# TRANSFORMER_RJ45.net
KiCad netlist of a schematic drawn in Altium Designer
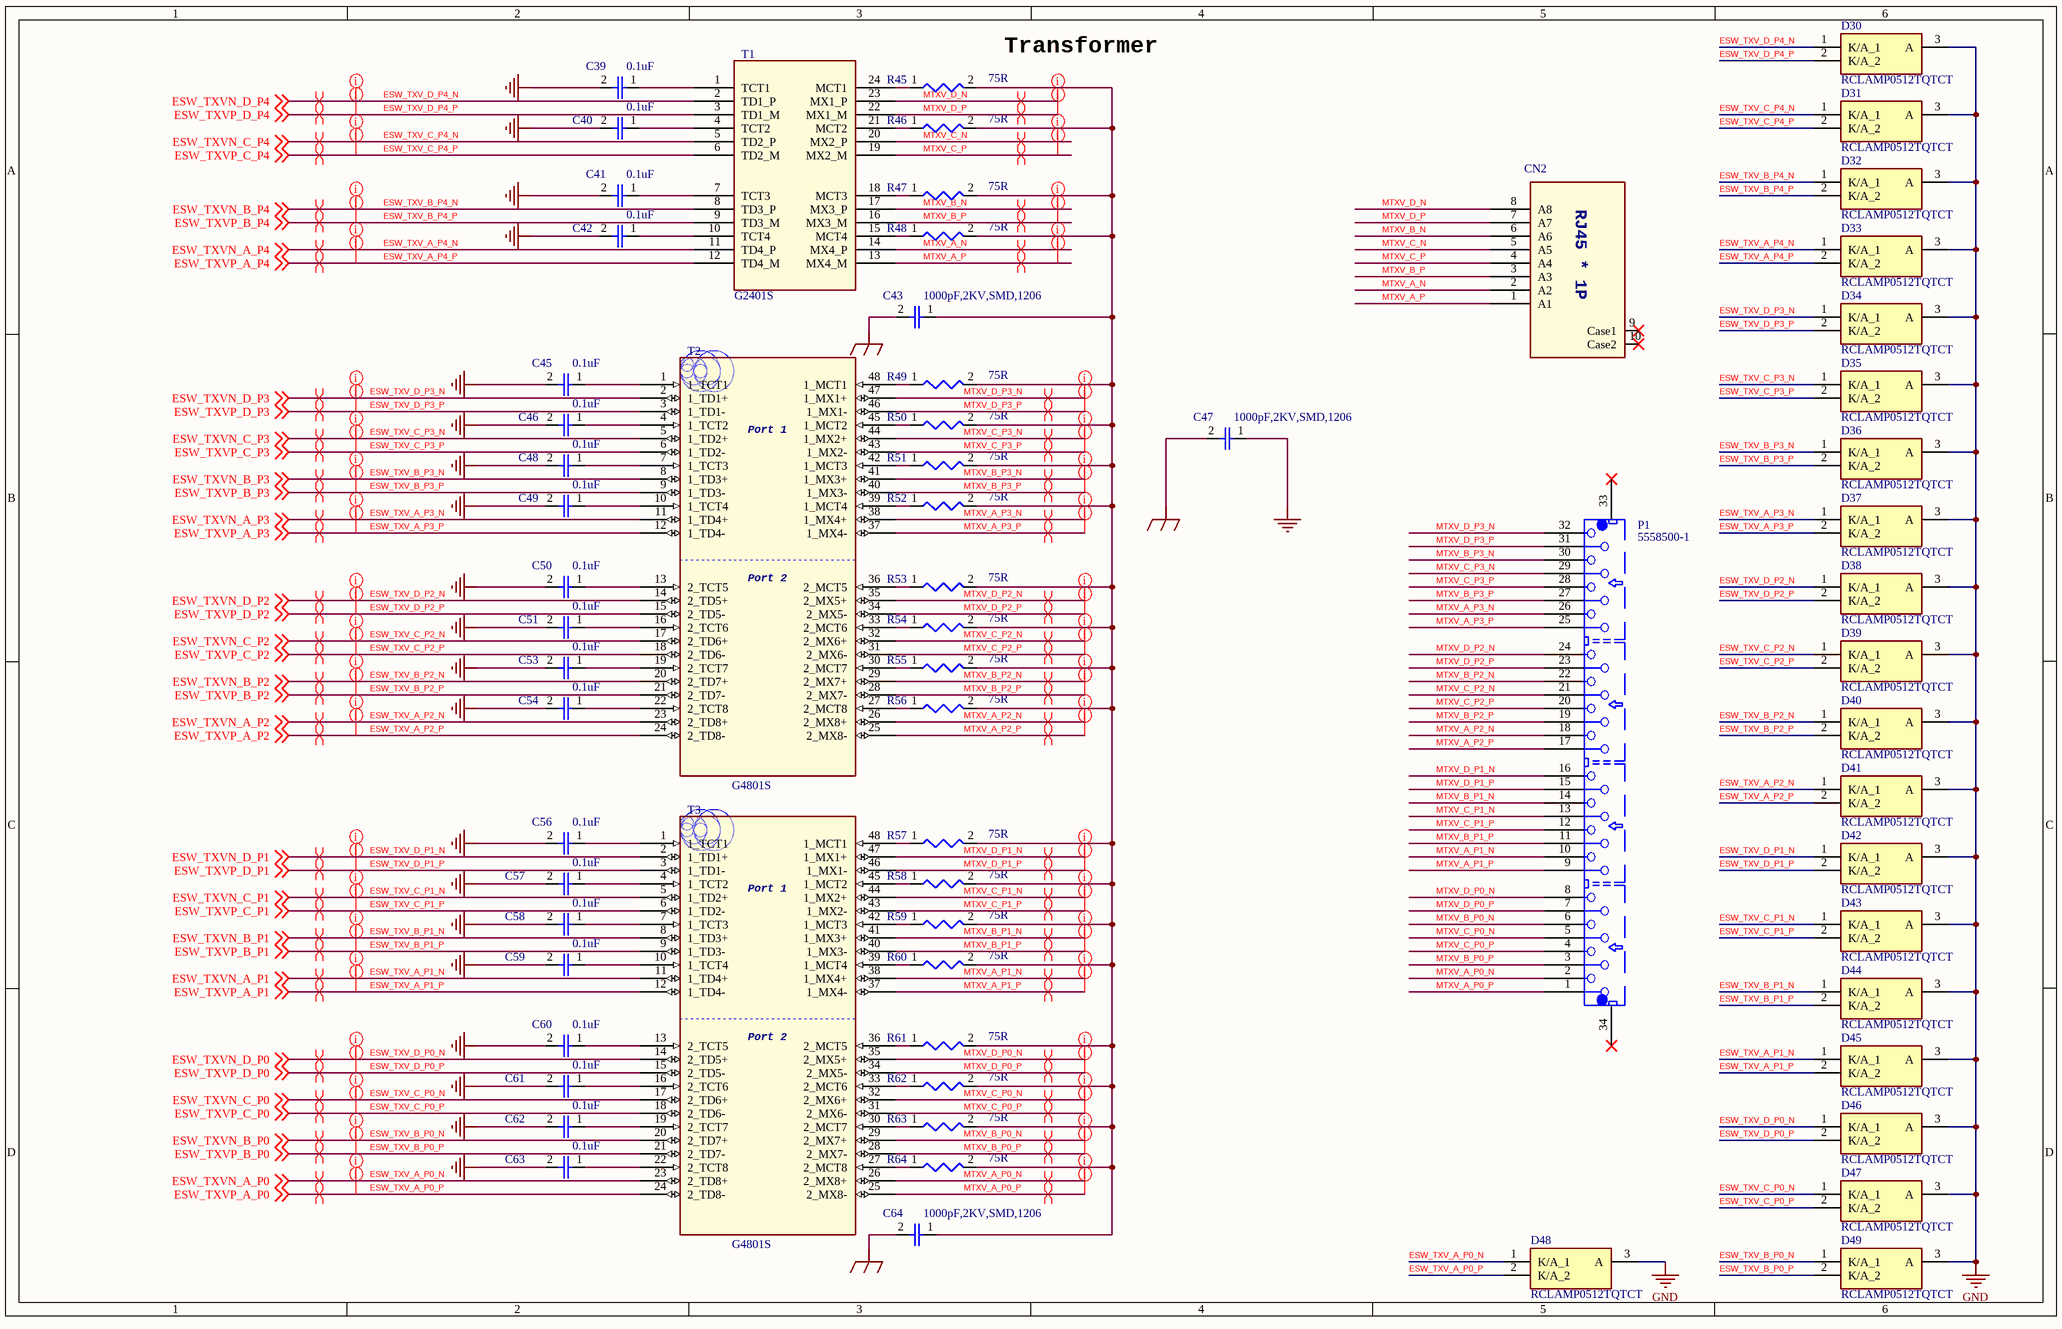
[diagram p0: TRANSFORMER_RJ45.SchDoc]

(export (version "E")
  (design (tool "Eeschema 10.0.6"))
  (components
    (comp (ref "C39") (value "0.1uF") (footprint "0402-C") (libsource (lib "OOLITEV8") (part "CAP")))
    (comp (ref "C40") (value "0.1uF") (footprint "0402-C") (libsource (lib "OOLITEV8") (part "CAP")))
    (comp (ref "C41") (value "0.1uF") (footprint "0402-C") (libsource (lib "OOLITEV8") (part "CAP")))
    (comp (ref "C42") (value "0.1uF") (footprint "0402-C") (libsource (lib "OOLITEV8") (part "CAP")))
    (comp (ref "C43")
      (value "1000pF,2KV,SMD,1206")
      (footprint "1206-C")
      (libsource (lib "OOLITEV8") (part "CAP"))
    )
    (comp (ref "C45") (value "0.1uF") (footprint "0402-C") (libsource (lib "OOLITEV8") (part "CAP")))
    (comp (ref "C46") (value "0.1uF") (footprint "0402-C") (libsource (lib "OOLITEV8") (part "CAP")))
    (comp (ref "C47")
      (value "1000pF,2KV,SMD,1206")
      (footprint "1206-C")
      (libsource (lib "OOLITEV8") (part "CAP"))
    )
    (comp (ref "C48") (value "0.1uF") (footprint "0402-C") (libsource (lib "OOLITEV8") (part "CAP")))
    (comp (ref "C49") (value "0.1uF") (footprint "0402-C") (libsource (lib "OOLITEV8") (part "CAP")))
    (comp (ref "C50") (value "0.1uF") (footprint "0402-C") (libsource (lib "OOLITEV8") (part "CAP")))
    (comp (ref "C51") (value "0.1uF") (footprint "0402-C") (libsource (lib "OOLITEV8") (part "CAP")))
    (comp (ref "C53") (value "0.1uF") (footprint "0402-C") (libsource (lib "OOLITEV8") (part "CAP")))
    (comp (ref "C54") (value "0.1uF") (footprint "0402-C") (libsource (lib "OOLITEV8") (part "CAP")))
    (comp (ref "C56") (value "0.1uF") (footprint "0402-C") (libsource (lib "OOLITEV8") (part "CAP")))
    (comp (ref "C57") (value "0.1uF") (footprint "0402-C") (libsource (lib "OOLITEV8") (part "CAP")))
    (comp (ref "C58") (value "0.1uF") (footprint "0402-C") (libsource (lib "OOLITEV8") (part "CAP")))
    (comp (ref "C59") (value "0.1uF") (footprint "0402-C") (libsource (lib "OOLITEV8") (part "CAP")))
    (comp (ref "C60") (value "0.1uF") (footprint "0402-C") (libsource (lib "OOLITEV8") (part "CAP")))
    (comp (ref "C61") (value "0.1uF") (footprint "0402-C") (libsource (lib "OOLITEV8") (part "CAP")))
    (comp (ref "C62") (value "0.1uF") (footprint "0402-C") (libsource (lib "OOLITEV8") (part "CAP")))
    (comp (ref "C63") (value "0.1uF") (footprint "0402-C") (libsource (lib "OOLITEV8") (part "CAP")))
    (comp (ref "C64")
      (value "1000pF,2KV,SMD,1206")
      (footprint "1206-C")
      (libsource (lib "OOLITEV8") (part "CAP"))
    )
    (comp (ref "CN2")
      (value "6116518-1")
      (footprint "BEL_SS-6488-NF")
      (libsource (lib "OOLITEV8") (part "6116518-1"))
    )
    (comp (ref "D30")
      (value "RCLAMP0512TQTCT")
      (footprint "RCLAMP0512TQTCT")
      (description "Diode")
      (fields (field (name "MOUSER PART NUMBER") "947-RCLAMP0512TQTCT"))
      (libsource (lib "SamacSys") (part "RCLAMP0512TQTCT"))
    )
    (comp (ref "D31")
      (value "RCLAMP0512TQTCT")
      (footprint "RCLAMP0512TQTCT")
      (description "Diode")
      (fields (field (name "MOUSER PART NUMBER") "947-RCLAMP0512TQTCT"))
      (libsource (lib "SamacSys") (part "RCLAMP0512TQTCT"))
    )
    (comp (ref "D32")
      (value "RCLAMP0512TQTCT")
      (footprint "RCLAMP0512TQTCT")
      (description "Diode")
      (fields (field (name "MOUSER PART NUMBER") "947-RCLAMP0512TQTCT"))
      (libsource (lib "SamacSys") (part "RCLAMP0512TQTCT"))
    )
    (comp (ref "D33")
      (value "RCLAMP0512TQTCT")
      (footprint "RCLAMP0512TQTCT")
      (description "Diode")
      (fields (field (name "MOUSER PART NUMBER") "947-RCLAMP0512TQTCT"))
      (libsource (lib "SamacSys") (part "RCLAMP0512TQTCT"))
    )
    (comp (ref "D34")
      (value "RCLAMP0512TQTCT")
      (footprint "RCLAMP0512TQTCT")
      (description "Diode")
      (fields (field (name "MOUSER PART NUMBER") "947-RCLAMP0512TQTCT"))
      (libsource (lib "SamacSys") (part "RCLAMP0512TQTCT"))
    )
    (comp (ref "D35")
      (value "RCLAMP0512TQTCT")
      (footprint "RCLAMP0512TQTCT")
      (description "Diode")
      (fields (field (name "MOUSER PART NUMBER") "947-RCLAMP0512TQTCT"))
      (libsource (lib "SamacSys") (part "RCLAMP0512TQTCT"))
    )
    (comp (ref "D36")
      (value "RCLAMP0512TQTCT")
      (footprint "RCLAMP0512TQTCT")
      (description "Diode")
      (fields (field (name "MOUSER PART NUMBER") "947-RCLAMP0512TQTCT"))
      (libsource (lib "SamacSys") (part "RCLAMP0512TQTCT"))
    )
    (comp (ref "D37")
      (value "RCLAMP0512TQTCT")
      (footprint "RCLAMP0512TQTCT")
      (description "Diode")
      (fields (field (name "MOUSER PART NUMBER") "947-RCLAMP0512TQTCT"))
      (libsource (lib "SamacSys") (part "RCLAMP0512TQTCT"))
    )
    (comp (ref "D38")
      (value "RCLAMP0512TQTCT")
      (footprint "RCLAMP0512TQTCT")
      (description "Diode")
      (fields (field (name "MOUSER PART NUMBER") "947-RCLAMP0512TQTCT"))
      (libsource (lib "SamacSys") (part "RCLAMP0512TQTCT"))
    )
    (comp (ref "D39")
      (value "RCLAMP0512TQTCT")
      (footprint "RCLAMP0512TQTCT")
      (description "Diode")
      (fields (field (name "MOUSER PART NUMBER") "947-RCLAMP0512TQTCT"))
      (libsource (lib "SamacSys") (part "RCLAMP0512TQTCT"))
    )
    (comp (ref "D40")
      (value "RCLAMP0512TQTCT")
      (footprint "RCLAMP0512TQTCT")
      (description "Diode")
      (fields (field (name "MOUSER PART NUMBER") "947-RCLAMP0512TQTCT"))
      (libsource (lib "SamacSys") (part "RCLAMP0512TQTCT"))
    )
    (comp (ref "D41")
      (value "RCLAMP0512TQTCT")
      (footprint "RCLAMP0512TQTCT")
      (description "Diode")
      (fields (field (name "MOUSER PART NUMBER") "947-RCLAMP0512TQTCT"))
      (libsource (lib "SamacSys") (part "RCLAMP0512TQTCT"))
    )
    (comp (ref "D42")
      (value "RCLAMP0512TQTCT")
      (footprint "RCLAMP0512TQTCT")
      (description "Diode")
      (fields (field (name "MOUSER PART NUMBER") "947-RCLAMP0512TQTCT"))
      (libsource (lib "SamacSys") (part "RCLAMP0512TQTCT"))
    )
    (comp (ref "D43")
      (value "RCLAMP0512TQTCT")
      (footprint "RCLAMP0512TQTCT")
      (description "Diode")
      (fields (field (name "MOUSER PART NUMBER") "947-RCLAMP0512TQTCT"))
      (libsource (lib "SamacSys") (part "RCLAMP0512TQTCT"))
    )
    (comp (ref "D44")
      (value "RCLAMP0512TQTCT")
      (footprint "RCLAMP0512TQTCT")
      (description "Diode")
      (fields (field (name "MOUSER PART NUMBER") "947-RCLAMP0512TQTCT"))
      (libsource (lib "SamacSys") (part "RCLAMP0512TQTCT"))
    )
    (comp (ref "D45")
      (value "RCLAMP0512TQTCT")
      (footprint "RCLAMP0512TQTCT")
      (description "Diode")
      (fields (field (name "MOUSER PART NUMBER") "947-RCLAMP0512TQTCT"))
      (libsource (lib "SamacSys") (part "RCLAMP0512TQTCT"))
    )
    (comp (ref "D46")
      (value "RCLAMP0512TQTCT")
      (footprint "RCLAMP0512TQTCT")
      (description "Diode")
      (fields (field (name "MOUSER PART NUMBER") "947-RCLAMP0512TQTCT"))
      (libsource (lib "SamacSys") (part "RCLAMP0512TQTCT"))
    )
    (comp (ref "D47")
      (value "RCLAMP0512TQTCT")
      (footprint "RCLAMP0512TQTCT")
      (description "Diode")
      (fields (field (name "MOUSER PART NUMBER") "947-RCLAMP0512TQTCT"))
      (libsource (lib "SamacSys") (part "RCLAMP0512TQTCT"))
    )
    (comp (ref "D48")
      (value "RCLAMP0512TQTCT")
      (footprint "RCLAMP0512TQTCT")
      (description "Diode")
      (fields (field (name "MOUSER PART NUMBER") "947-RCLAMP0512TQTCT"))
      (libsource (lib "SamacSys") (part "RCLAMP0512TQTCT"))
    )
    (comp (ref "D49")
      (value "RCLAMP0512TQTCT")
      (footprint "RCLAMP0512TQTCT")
      (description "Diode")
      (fields (field (name "MOUSER PART NUMBER") "947-RCLAMP0512TQTCT"))
      (libsource (lib "SamacSys") (part "RCLAMP0512TQTCT"))
    )
    (comp (ref "P1")
      (value "5558500-1")
      (footprint "CONN_ARJ14A-MESA-MU2")
      (libsource (lib "OOLITEV8") (part "5558500-1"))
    )
    (comp (ref "R45") (value "75R") (footprint "0402-R") (libsource (lib "OOLITEV8") (part "Res")))
    (comp (ref "R46") (value "75R") (footprint "0402-R") (libsource (lib "OOLITEV8") (part "Res")))
    (comp (ref "R47") (value "75R") (footprint "0402-R") (libsource (lib "OOLITEV8") (part "Res")))
    (comp (ref "R48") (value "75R") (footprint "0402-R") (libsource (lib "OOLITEV8") (part "Res")))
    (comp (ref "R49") (value "75R") (footprint "0402-R") (libsource (lib "OOLITEV8") (part "Res")))
    (comp (ref "R50") (value "75R") (footprint "0402-R") (libsource (lib "OOLITEV8") (part "Res")))
    (comp (ref "R51") (value "75R") (footprint "0402-R") (libsource (lib "OOLITEV8") (part "Res")))
    (comp (ref "R52") (value "75R") (footprint "0402-R") (libsource (lib "OOLITEV8") (part "Res")))
    (comp (ref "R53") (value "75R") (footprint "0402-R") (libsource (lib "OOLITEV8") (part "Res")))
    (comp (ref "R54") (value "75R") (footprint "0402-R") (libsource (lib "OOLITEV8") (part "Res")))
    (comp (ref "R55") (value "75R") (footprint "0402-R") (libsource (lib "OOLITEV8") (part "Res")))
    (comp (ref "R56") (value "75R") (footprint "0402-R") (libsource (lib "OOLITEV8") (part "Res")))
    (comp (ref "R57") (value "75R") (footprint "0402-R") (libsource (lib "OOLITEV8") (part "Res")))
    (comp (ref "R58") (value "75R") (footprint "0402-R") (libsource (lib "OOLITEV8") (part "Res")))
    (comp (ref "R59") (value "75R") (footprint "0402-R") (libsource (lib "OOLITEV8") (part "Res")))
    (comp (ref "R60") (value "75R") (footprint "0402-R") (libsource (lib "OOLITEV8") (part "Res")))
    (comp (ref "R61") (value "75R") (footprint "0402-R") (libsource (lib "OOLITEV8") (part "Res")))
    (comp (ref "R62") (value "75R") (footprint "0402-R") (libsource (lib "OOLITEV8") (part "Res")))
    (comp (ref "R63") (value "75R") (footprint "0402-R") (libsource (lib "OOLITEV8") (part "Res")))
    (comp (ref "R64") (value "75R") (footprint "0402-R") (libsource (lib "OOLITEV8") (part "Res")))
    (comp (ref "T1")
      (value "G2401S")
      (footprint "SOP127P1600X572-24N")
      (description "Audio Transformers / Signal Transformers 1000BaseT SMD NonPoE 350uH .65Ohms 1-Por")
      (libsource (lib "OOLITEV8") (part "G2401S"))
    )
    (comp (ref "T2")
      (value "G4801S")
      (footprint "NV6")
      (description "Audio Transformers / Signal Transformers GIGABIT ISO MOD SMD 48P 2-Port w/Choke")
      (libsource (lib "OOLITEV8") (part "G4801S"))
    )
    (comp (ref "T3")
      (value "G4801S")
      (footprint "NV6")
      (description "Audio Transformers / Signal Transformers GIGABIT ISO MOD SMD 48P 2-Port w/Choke")
      (libsource (lib "OOLITEV8") (part "G4801S"))
    )
  )
  (nets
    (net (code "1") (name "/MTXV_A_N") (class "Default")
      (node (ref "CN2") (pin "2") (pinfunction "A2_2") (pintype "passive"))
      (node (ref "T1") (pin "14") (pinfunction "MX4_P_14") (pintype "passive"))
    )
    (net (code "2") (name "/MTXV_A_P") (class "Default")
      (node (ref "CN2") (pin "1") (pinfunction "A1_1") (pintype "passive"))
      (node (ref "T1") (pin "13") (pinfunction "MX4_M_13") (pintype "passive"))
    )
    (net (code "3") (name "/MTXV_A_P0_N") (class "Default")
      (node (ref "P1") (pin "2") (pinfunction "2_2") (pintype "passive"))
      (node (ref "T3") (pin "26") (pinfunction "2_MX8+_26") (pintype "bidirectional"))
    )
    (net (code "4") (name "/MTXV_A_P0_P") (class "Default")
      (node (ref "P1") (pin "1") (pinfunction "1_1") (pintype "passive"))
      (node (ref "T3") (pin "25") (pinfunction "2_MX8-_25") (pintype "bidirectional"))
    )
    (net (code "5") (name "/MTXV_A_P1_N") (class "Default")
      (node (ref "P1") (pin "10") (pinfunction "10_10") (pintype "passive"))
      (node (ref "T3") (pin "38") (pinfunction "1_MX4+_38") (pintype "bidirectional"))
    )
    (net (code "6") (name "/MTXV_A_P1_P") (class "Default")
      (node (ref "P1") (pin "9") (pinfunction "9_9") (pintype "passive"))
      (node (ref "T3") (pin "37") (pinfunction "1_MX4-_37") (pintype "bidirectional"))
    )
    (net (code "7") (name "/MTXV_A_P2_N") (class "Default")
      (node (ref "P1") (pin "18") (pinfunction "18_18") (pintype "passive"))
      (node (ref "T2") (pin "26") (pinfunction "2_MX8+_26") (pintype "bidirectional"))
    )
    (net (code "8") (name "/MTXV_A_P2_P") (class "Default")
      (node (ref "P1") (pin "17") (pinfunction "17_17") (pintype "passive"))
      (node (ref "T2") (pin "25") (pinfunction "2_MX8-_25") (pintype "bidirectional"))
    )
    (net (code "9") (name "/MTXV_A_P3_N") (class "Default")
      (node (ref "P1") (pin "26") (pinfunction "26_26") (pintype "passive"))
      (node (ref "T2") (pin "38") (pinfunction "1_MX4+_38") (pintype "bidirectional"))
    )
    (net (code "10") (name "/MTXV_A_P3_P") (class "Default")
      (node (ref "P1") (pin "25") (pinfunction "25_25") (pintype "passive"))
      (node (ref "T2") (pin "37") (pinfunction "1_MX4-_37") (pintype "bidirectional"))
    )
    (net (code "11") (name "/MTXV_B_N") (class "Default")
      (node (ref "CN2") (pin "6") (pinfunction "A6_6") (pintype "passive"))
      (node (ref "T1") (pin "17") (pinfunction "MX3_P_17") (pintype "passive"))
    )
    (net (code "12") (name "/MTXV_B_P") (class "Default")
      (node (ref "CN2") (pin "3") (pinfunction "A3_3") (pintype "passive"))
      (node (ref "T1") (pin "16") (pinfunction "MX3_M_16") (pintype "passive"))
    )
    (net (code "13") (name "/MTXV_B_P0_N") (class "Default")
      (node (ref "P1") (pin "6") (pinfunction "6_6") (pintype "passive"))
      (node (ref "T3") (pin "29") (pinfunction "2_MX7+_29") (pintype "bidirectional"))
    )
    (net (code "14") (name "/MTXV_B_P0_P") (class "Default")
      (node (ref "P1") (pin "3") (pinfunction "3_3") (pintype "passive"))
      (node (ref "T3") (pin "28") (pinfunction "2_MX7-_28") (pintype "bidirectional"))
    )
    (net (code "15") (name "/MTXV_B_P1_N") (class "Default")
      (node (ref "P1") (pin "14") (pinfunction "14_14") (pintype "passive"))
      (node (ref "T3") (pin "41") (pinfunction "1_MX3+_41") (pintype "bidirectional"))
    )
    (net (code "16") (name "/MTXV_B_P1_P") (class "Default")
      (node (ref "P1") (pin "11") (pinfunction "11_11") (pintype "passive"))
      (node (ref "T3") (pin "40") (pinfunction "1_MX3-_40") (pintype "bidirectional"))
    )
    (net (code "17") (name "/MTXV_B_P2_N") (class "Default")
      (node (ref "P1") (pin "22") (pinfunction "22_22") (pintype "passive"))
      (node (ref "T2") (pin "29") (pinfunction "2_MX7+_29") (pintype "bidirectional"))
    )
    (net (code "18") (name "/MTXV_B_P2_P") (class "Default")
      (node (ref "P1") (pin "19") (pinfunction "19_19") (pintype "passive"))
      (node (ref "T2") (pin "28") (pinfunction "2_MX7-_28") (pintype "bidirectional"))
    )
    (net (code "19") (name "/MTXV_B_P3_N") (class "Default")
      (node (ref "P1") (pin "30") (pinfunction "30_30") (pintype "passive"))
      (node (ref "T2") (pin "41") (pinfunction "1_MX3+_41") (pintype "bidirectional"))
    )
    (net (code "20") (name "/MTXV_B_P3_P") (class "Default")
      (node (ref "P1") (pin "27") (pinfunction "27_27") (pintype "passive"))
      (node (ref "T2") (pin "40") (pinfunction "1_MX3-_40") (pintype "bidirectional"))
    )
    (net (code "21") (name "/MTXV_C_N") (class "Default")
      (node (ref "CN2") (pin "5") (pinfunction "A5_5") (pintype "passive"))
      (node (ref "T1") (pin "20") (pinfunction "MX2_P_20") (pintype "passive"))
    )
    (net (code "22") (name "/MTXV_C_P") (class "Default")
      (node (ref "CN2") (pin "4") (pinfunction "A4_4") (pintype "passive"))
      (node (ref "T1") (pin "19") (pinfunction "MX2_M_19") (pintype "passive"))
    )
    (net (code "23") (name "/MTXV_C_P0_N") (class "Default")
      (node (ref "P1") (pin "5") (pinfunction "5_5") (pintype "passive"))
      (node (ref "T3") (pin "32") (pinfunction "2_MX6+_32") (pintype "bidirectional"))
    )
    (net (code "24") (name "/MTXV_C_P0_P") (class "Default")
      (node (ref "P1") (pin "4") (pinfunction "4_4") (pintype "passive"))
      (node (ref "T3") (pin "31") (pinfunction "2_MX6-_31") (pintype "bidirectional"))
    )
    (net (code "25") (name "/MTXV_C_P1_N") (class "Default")
      (node (ref "P1") (pin "13") (pinfunction "13_13") (pintype "passive"))
      (node (ref "T3") (pin "44") (pinfunction "1_MX2+_44") (pintype "bidirectional"))
    )
    (net (code "26") (name "/MTXV_C_P1_P") (class "Default")
      (node (ref "P1") (pin "12") (pinfunction "12_12") (pintype "passive"))
      (node (ref "T3") (pin "43") (pinfunction "1_MX2-_43") (pintype "bidirectional"))
    )
    (net (code "27") (name "/MTXV_C_P2_N") (class "Default")
      (node (ref "P1") (pin "21") (pinfunction "21_21") (pintype "passive"))
      (node (ref "T2") (pin "32") (pinfunction "2_MX6+_32") (pintype "bidirectional"))
    )
    (net (code "28") (name "/MTXV_C_P2_P") (class "Default")
      (node (ref "P1") (pin "20") (pinfunction "20_20") (pintype "passive"))
      (node (ref "T2") (pin "31") (pinfunction "2_MX6-_31") (pintype "bidirectional"))
    )
    (net (code "29") (name "/MTXV_C_P3_N") (class "Default")
      (node (ref "P1") (pin "29") (pinfunction "29_29") (pintype "passive"))
      (node (ref "T2") (pin "44") (pinfunction "1_MX2+_44") (pintype "bidirectional"))
    )
    (net (code "30") (name "/MTXV_C_P3_P") (class "Default")
      (node (ref "P1") (pin "28") (pinfunction "28_28") (pintype "passive"))
      (node (ref "T2") (pin "43") (pinfunction "1_MX2-_43") (pintype "bidirectional"))
    )
    (net (code "31") (name "/MTXV_D_N") (class "Default")
      (node (ref "CN2") (pin "8") (pinfunction "A8_8") (pintype "passive"))
      (node (ref "T1") (pin "23") (pinfunction "MX1_P_23") (pintype "passive"))
    )
    (net (code "32") (name "/MTXV_D_P") (class "Default")
      (node (ref "CN2") (pin "7") (pinfunction "A7_7") (pintype "passive"))
      (node (ref "T1") (pin "22") (pinfunction "MX1_M_22") (pintype "passive"))
    )
    (net (code "33") (name "/MTXV_D_P0_N") (class "Default")
      (node (ref "P1") (pin "8") (pinfunction "8_8") (pintype "passive"))
      (node (ref "T3") (pin "35") (pinfunction "2_MX5+_35") (pintype "bidirectional"))
    )
    (net (code "34") (name "/MTXV_D_P0_P") (class "Default")
      (node (ref "P1") (pin "7") (pinfunction "7_7") (pintype "passive"))
      (node (ref "T3") (pin "34") (pinfunction "2_MX5-_34") (pintype "bidirectional"))
    )
    (net (code "35") (name "/MTXV_D_P1_N") (class "Default")
      (node (ref "P1") (pin "16") (pinfunction "16_16") (pintype "passive"))
      (node (ref "T3") (pin "47") (pinfunction "1_MX1+_47") (pintype "bidirectional"))
    )
    (net (code "36") (name "/MTXV_D_P1_P") (class "Default")
      (node (ref "P1") (pin "15") (pinfunction "15_15") (pintype "passive"))
      (node (ref "T3") (pin "46") (pinfunction "1_MX1-_46") (pintype "bidirectional"))
    )
    (net (code "37") (name "/MTXV_D_P2_N") (class "Default")
      (node (ref "P1") (pin "24") (pinfunction "24_24") (pintype "passive"))
      (node (ref "T2") (pin "35") (pinfunction "2_MX5+_35") (pintype "bidirectional"))
    )
    (net (code "38") (name "/MTXV_D_P2_P") (class "Default")
      (node (ref "P1") (pin "23") (pinfunction "23_23") (pintype "passive"))
      (node (ref "T2") (pin "34") (pinfunction "2_MX5-_34") (pintype "bidirectional"))
    )
    (net (code "39") (name "/MTXV_D_P3_N") (class "Default")
      (node (ref "P1") (pin "32") (pinfunction "32_32") (pintype "passive"))
      (node (ref "T2") (pin "47") (pinfunction "1_MX1+_47") (pintype "bidirectional"))
    )
    (net (code "40") (name "/MTXV_D_P3_P") (class "Default")
      (node (ref "P1") (pin "31") (pinfunction "31_31") (pintype "passive"))
      (node (ref "T2") (pin "46") (pinfunction "1_MX1-_46") (pintype "bidirectional"))
    )
    (net (code "41") (name "CHGND_GE_A") (class "Default")
      (node (ref "C43") (pin "2") (pinfunction "2_2") (pintype "passive"))
      (node (ref "C47") (pin "2") (pinfunction "2_2") (pintype "passive"))
      (node (ref "C64") (pin "2") (pinfunction "2_2") (pintype "passive"))
    )
    (net (code "42") (name "ESW_TXVN_A_P0") (class "Default")
      (node (ref "D48") (pin "1") (pinfunction "K/A_1_1") (pintype "passive"))
      (node (ref "T3") (pin "23") (pinfunction "2_TD8+_23") (pintype "bidirectional"))
    )
    (net (code "43") (name "ESW_TXVN_A_P1") (class "Default")
      (node (ref "D45") (pin "1") (pinfunction "K/A_1_1") (pintype "passive"))
      (node (ref "T3") (pin "11") (pinfunction "1_TD4+_11") (pintype "bidirectional"))
    )
    (net (code "44") (name "ESW_TXVN_A_P2") (class "Default")
      (node (ref "D41") (pin "1") (pinfunction "K/A_1_1") (pintype "passive"))
      (node (ref "T2") (pin "23") (pinfunction "2_TD8+_23") (pintype "bidirectional"))
    )
    (net (code "45") (name "ESW_TXVN_A_P3") (class "Default")
      (node (ref "D37") (pin "1") (pinfunction "K/A_1_1") (pintype "passive"))
      (node (ref "T2") (pin "11") (pinfunction "1_TD4+_11") (pintype "bidirectional"))
    )
    (net (code "46") (name "ESW_TXVN_A_P4") (class "Default")
      (node (ref "D33") (pin "1") (pinfunction "K/A_1_1") (pintype "passive"))
      (node (ref "T1") (pin "11") (pinfunction "TD4_P_11") (pintype "passive"))
    )
    (net (code "47") (name "ESW_TXVN_B_P0") (class "Default")
      (node (ref "D49") (pin "1") (pinfunction "K/A_1_1") (pintype "passive"))
      (node (ref "T3") (pin "20") (pinfunction "2_TD7+_20") (pintype "bidirectional"))
    )
    (net (code "48") (name "ESW_TXVN_B_P1") (class "Default")
      (node (ref "D44") (pin "1") (pinfunction "K/A_1_1") (pintype "passive"))
      (node (ref "T3") (pin "8") (pinfunction "1_TD3+_8") (pintype "bidirectional"))
    )
    (net (code "49") (name "ESW_TXVN_B_P2") (class "Default")
      (node (ref "D40") (pin "1") (pinfunction "K/A_1_1") (pintype "passive"))
      (node (ref "T2") (pin "20") (pinfunction "2_TD7+_20") (pintype "bidirectional"))
    )
    (net (code "50") (name "ESW_TXVN_B_P3") (class "Default")
      (node (ref "D36") (pin "1") (pinfunction "K/A_1_1") (pintype "passive"))
      (node (ref "T2") (pin "8") (pinfunction "1_TD3+_8") (pintype "bidirectional"))
    )
    (net (code "51") (name "ESW_TXVN_B_P4") (class "Default")
      (node (ref "D32") (pin "1") (pinfunction "K/A_1_1") (pintype "passive"))
      (node (ref "T1") (pin "8") (pinfunction "TD3_P_8") (pintype "passive"))
    )
    (net (code "52") (name "ESW_TXVN_C_P0") (class "Default")
      (node (ref "D47") (pin "1") (pinfunction "K/A_1_1") (pintype "passive"))
      (node (ref "T3") (pin "17") (pinfunction "2_TD6+_17") (pintype "bidirectional"))
    )
    (net (code "53") (name "ESW_TXVN_C_P1") (class "Default")
      (node (ref "D43") (pin "1") (pinfunction "K/A_1_1") (pintype "passive"))
      (node (ref "T3") (pin "5") (pinfunction "1_TD2+_5") (pintype "bidirectional"))
    )
    (net (code "54") (name "ESW_TXVN_C_P2") (class "Default")
      (node (ref "D39") (pin "1") (pinfunction "K/A_1_1") (pintype "passive"))
      (node (ref "T2") (pin "17") (pinfunction "2_TD6+_17") (pintype "bidirectional"))
    )
    (net (code "55") (name "ESW_TXVN_C_P3") (class "Default")
      (node (ref "D35") (pin "1") (pinfunction "K/A_1_1") (pintype "passive"))
      (node (ref "T2") (pin "5") (pinfunction "1_TD2+_5") (pintype "bidirectional"))
    )
    (net (code "56") (name "ESW_TXVN_C_P4") (class "Default")
      (node (ref "D31") (pin "1") (pinfunction "K/A_1_1") (pintype "passive"))
      (node (ref "T1") (pin "5") (pinfunction "TD2_P_5") (pintype "passive"))
    )
    (net (code "57") (name "ESW_TXVN_D_P0") (class "Default")
      (node (ref "D46") (pin "1") (pinfunction "K/A_1_1") (pintype "passive"))
      (node (ref "T3") (pin "14") (pinfunction "2_TD5+_14") (pintype "bidirectional"))
    )
    (net (code "58") (name "ESW_TXVN_D_P1") (class "Default")
      (node (ref "D42") (pin "1") (pinfunction "K/A_1_1") (pintype "passive"))
      (node (ref "T3") (pin "2") (pinfunction "1_TD1+_2") (pintype "bidirectional"))
    )
    (net (code "59") (name "ESW_TXVN_D_P2") (class "Default")
      (node (ref "D38") (pin "1") (pinfunction "K/A_1_1") (pintype "passive"))
      (node (ref "T2") (pin "14") (pinfunction "2_TD5+_14") (pintype "bidirectional"))
    )
    (net (code "60") (name "ESW_TXVN_D_P3") (class "Default")
      (node (ref "D34") (pin "1") (pinfunction "K/A_1_1") (pintype "passive"))
      (node (ref "T2") (pin "2") (pinfunction "1_TD1+_2") (pintype "bidirectional"))
    )
    (net (code "61") (name "ESW_TXVN_D_P4") (class "Default")
      (node (ref "D30") (pin "1") (pinfunction "K/A_1_1") (pintype "passive"))
      (node (ref "T1") (pin "2") (pinfunction "TD1_P_2") (pintype "passive"))
    )
    (net (code "62") (name "ESW_TXVP_A_P0") (class "Default")
      (node (ref "D48") (pin "2") (pinfunction "K/A_2_2") (pintype "passive"))
      (node (ref "T3") (pin "24") (pinfunction "2_TD8-_24") (pintype "bidirectional"))
    )
    (net (code "63") (name "ESW_TXVP_A_P1") (class "Default")
      (node (ref "D45") (pin "2") (pinfunction "K/A_2_2") (pintype "passive"))
      (node (ref "T3") (pin "12") (pinfunction "1_TD4-_12") (pintype "bidirectional"))
    )
    (net (code "64") (name "ESW_TXVP_A_P2") (class "Default")
      (node (ref "D41") (pin "2") (pinfunction "K/A_2_2") (pintype "passive"))
      (node (ref "T2") (pin "24") (pinfunction "2_TD8-_24") (pintype "bidirectional"))
    )
    (net (code "65") (name "ESW_TXVP_A_P3") (class "Default")
      (node (ref "D37") (pin "2") (pinfunction "K/A_2_2") (pintype "passive"))
      (node (ref "T2") (pin "12") (pinfunction "1_TD4-_12") (pintype "bidirectional"))
    )
    (net (code "66") (name "ESW_TXVP_A_P4") (class "Default")
      (node (ref "D33") (pin "2") (pinfunction "K/A_2_2") (pintype "passive"))
      (node (ref "T1") (pin "12") (pinfunction "TD4_M_12") (pintype "passive"))
    )
    (net (code "67") (name "ESW_TXVP_B_P0") (class "Default")
      (node (ref "D49") (pin "2") (pinfunction "K/A_2_2") (pintype "passive"))
      (node (ref "T3") (pin "21") (pinfunction "2_TD7-_21") (pintype "bidirectional"))
    )
    (net (code "68") (name "ESW_TXVP_B_P1") (class "Default")
      (node (ref "D44") (pin "2") (pinfunction "K/A_2_2") (pintype "passive"))
      (node (ref "T3") (pin "9") (pinfunction "1_TD3-_9") (pintype "bidirectional"))
    )
    (net (code "69") (name "ESW_TXVP_B_P2") (class "Default")
      (node (ref "D40") (pin "2") (pinfunction "K/A_2_2") (pintype "passive"))
      (node (ref "T2") (pin "21") (pinfunction "2_TD7-_21") (pintype "bidirectional"))
    )
    (net (code "70") (name "ESW_TXVP_B_P3") (class "Default")
      (node (ref "D36") (pin "2") (pinfunction "K/A_2_2") (pintype "passive"))
      (node (ref "T2") (pin "9") (pinfunction "1_TD3-_9") (pintype "bidirectional"))
    )
    (net (code "71") (name "ESW_TXVP_B_P4") (class "Default")
      (node (ref "D32") (pin "2") (pinfunction "K/A_2_2") (pintype "passive"))
      (node (ref "T1") (pin "9") (pinfunction "TD3_M_9") (pintype "passive"))
    )
    (net (code "72") (name "ESW_TXVP_C_P0") (class "Default")
      (node (ref "D47") (pin "2") (pinfunction "K/A_2_2") (pintype "passive"))
      (node (ref "T3") (pin "18") (pinfunction "2_TD6-_18") (pintype "bidirectional"))
    )
    (net (code "73") (name "ESW_TXVP_C_P1") (class "Default")
      (node (ref "D43") (pin "2") (pinfunction "K/A_2_2") (pintype "passive"))
      (node (ref "T3") (pin "6") (pinfunction "1_TD2-_6") (pintype "bidirectional"))
    )
    (net (code "74") (name "ESW_TXVP_C_P2") (class "Default")
      (node (ref "D39") (pin "2") (pinfunction "K/A_2_2") (pintype "passive"))
      (node (ref "T2") (pin "18") (pinfunction "2_TD6-_18") (pintype "bidirectional"))
    )
    (net (code "75") (name "ESW_TXVP_C_P3") (class "Default")
      (node (ref "D35") (pin "2") (pinfunction "K/A_2_2") (pintype "passive"))
      (node (ref "T2") (pin "6") (pinfunction "1_TD2-_6") (pintype "bidirectional"))
    )
    (net (code "76") (name "ESW_TXVP_C_P4") (class "Default")
      (node (ref "D31") (pin "2") (pinfunction "K/A_2_2") (pintype "passive"))
      (node (ref "T1") (pin "6") (pinfunction "TD2_M_6") (pintype "passive"))
    )
    (net (code "77") (name "ESW_TXVP_D_P0") (class "Default")
      (node (ref "D46") (pin "2") (pinfunction "K/A_2_2") (pintype "passive"))
      (node (ref "T3") (pin "15") (pinfunction "2_TD5-_15") (pintype "bidirectional"))
    )
    (net (code "78") (name "ESW_TXVP_D_P1") (class "Default")
      (node (ref "D42") (pin "2") (pinfunction "K/A_2_2") (pintype "passive"))
      (node (ref "T3") (pin "3") (pinfunction "1_TD1-_3") (pintype "bidirectional"))
    )
    (net (code "79") (name "ESW_TXVP_D_P2") (class "Default")
      (node (ref "D38") (pin "2") (pinfunction "K/A_2_2") (pintype "passive"))
      (node (ref "T2") (pin "15") (pinfunction "2_TD5-_15") (pintype "bidirectional"))
    )
    (net (code "80") (name "ESW_TXVP_D_P3") (class "Default")
      (node (ref "D34") (pin "2") (pinfunction "K/A_2_2") (pintype "passive"))
      (node (ref "T2") (pin "3") (pinfunction "1_TD1-_3") (pintype "bidirectional"))
    )
    (net (code "81") (name "ESW_TXVP_D_P4") (class "Default")
      (node (ref "D30") (pin "2") (pinfunction "K/A_2_2") (pintype "passive"))
      (node (ref "T1") (pin "3") (pinfunction "TD1_M_3") (pintype "passive"))
    )
    (net (code "82") (name "GND") (class "Default")
      (node (ref "C39") (pin "2") (pinfunction "2_2") (pintype "passive"))
      (node (ref "C40") (pin "2") (pinfunction "2_2") (pintype "passive"))
      (node (ref "C41") (pin "2") (pinfunction "2_2") (pintype "passive"))
      (node (ref "C42") (pin "2") (pinfunction "2_2") (pintype "passive"))
      (node (ref "C45") (pin "2") (pinfunction "2_2") (pintype "passive"))
      (node (ref "C46") (pin "2") (pinfunction "2_2") (pintype "passive"))
      (node (ref "C47") (pin "1") (pinfunction "1_1") (pintype "passive"))
      (node (ref "C48") (pin "2") (pinfunction "2_2") (pintype "passive"))
      (node (ref "C49") (pin "2") (pinfunction "2_2") (pintype "passive"))
      (node (ref "C50") (pin "2") (pinfunction "2_2") (pintype "passive"))
      (node (ref "C51") (pin "2") (pinfunction "2_2") (pintype "passive"))
      (node (ref "C53") (pin "2") (pinfunction "2_2") (pintype "passive"))
      (node (ref "C54") (pin "2") (pinfunction "2_2") (pintype "passive"))
      (node (ref "C56") (pin "2") (pinfunction "2_2") (pintype "passive"))
      (node (ref "C57") (pin "2") (pinfunction "2_2") (pintype "passive"))
      (node (ref "C58") (pin "2") (pinfunction "2_2") (pintype "passive"))
      (node (ref "C59") (pin "2") (pinfunction "2_2") (pintype "passive"))
      (node (ref "C60") (pin "2") (pinfunction "2_2") (pintype "passive"))
      (node (ref "C61") (pin "2") (pinfunction "2_2") (pintype "passive"))
      (node (ref "C62") (pin "2") (pinfunction "2_2") (pintype "passive"))
      (node (ref "C63") (pin "2") (pinfunction "2_2") (pintype "passive"))
      (node (ref "D30") (pin "3") (pinfunction "A_3") (pintype "passive"))
      (node (ref "D31") (pin "3") (pinfunction "A_3") (pintype "passive"))
      (node (ref "D32") (pin "3") (pinfunction "A_3") (pintype "passive"))
      (node (ref "D33") (pin "3") (pinfunction "A_3") (pintype "passive"))
      (node (ref "D34") (pin "3") (pinfunction "A_3") (pintype "passive"))
      (node (ref "D35") (pin "3") (pinfunction "A_3") (pintype "passive"))
      (node (ref "D36") (pin "3") (pinfunction "A_3") (pintype "passive"))
      (node (ref "D37") (pin "3") (pinfunction "A_3") (pintype "passive"))
      (node (ref "D38") (pin "3") (pinfunction "A_3") (pintype "passive"))
      (node (ref "D39") (pin "3") (pinfunction "A_3") (pintype "passive"))
      (node (ref "D40") (pin "3") (pinfunction "A_3") (pintype "passive"))
      (node (ref "D41") (pin "3") (pinfunction "A_3") (pintype "passive"))
      (node (ref "D42") (pin "3") (pinfunction "A_3") (pintype "passive"))
      (node (ref "D43") (pin "3") (pinfunction "A_3") (pintype "passive"))
      (node (ref "D44") (pin "3") (pinfunction "A_3") (pintype "passive"))
      (node (ref "D45") (pin "3") (pinfunction "A_3") (pintype "passive"))
      (node (ref "D46") (pin "3") (pinfunction "A_3") (pintype "passive"))
      (node (ref "D47") (pin "3") (pinfunction "A_3") (pintype "passive"))
      (node (ref "D48") (pin "3") (pinfunction "A_3") (pintype "passive"))
      (node (ref "D49") (pin "3") (pinfunction "A_3") (pintype "passive"))
    )
    (net (code "83") (name "Net-(C43-Pad1)") (class "Default")
      (node (ref "C43") (pin "1") (pinfunction "1_1") (pintype "passive"))
      (node (ref "C64") (pin "1") (pinfunction "1_1") (pintype "passive"))
      (node (ref "R45") (pin "2") (pinfunction "2_2") (pintype "passive"))
      (node (ref "R46") (pin "2") (pinfunction "2_2") (pintype "passive"))
      (node (ref "R47") (pin "2") (pinfunction "2_2") (pintype "passive"))
      (node (ref "R48") (pin "2") (pinfunction "2_2") (pintype "passive"))
      (node (ref "R49") (pin "2") (pinfunction "2_2") (pintype "passive"))
      (node (ref "R50") (pin "2") (pinfunction "2_2") (pintype "passive"))
      (node (ref "R51") (pin "2") (pinfunction "2_2") (pintype "passive"))
      (node (ref "R52") (pin "2") (pinfunction "2_2") (pintype "passive"))
      (node (ref "R53") (pin "2") (pinfunction "2_2") (pintype "passive"))
      (node (ref "R54") (pin "2") (pinfunction "2_2") (pintype "passive"))
      (node (ref "R55") (pin "2") (pinfunction "2_2") (pintype "passive"))
      (node (ref "R56") (pin "2") (pinfunction "2_2") (pintype "passive"))
      (node (ref "R57") (pin "2") (pinfunction "2_2") (pintype "passive"))
      (node (ref "R58") (pin "2") (pinfunction "2_2") (pintype "passive"))
      (node (ref "R59") (pin "2") (pinfunction "2_2") (pintype "passive"))
      (node (ref "R60") (pin "2") (pinfunction "2_2") (pintype "passive"))
      (node (ref "R61") (pin "2") (pinfunction "2_2") (pintype "passive"))
      (node (ref "R62") (pin "2") (pinfunction "2_2") (pintype "passive"))
      (node (ref "R63") (pin "2") (pinfunction "2_2") (pintype "passive"))
      (node (ref "R64") (pin "2") (pinfunction "2_2") (pintype "passive"))
    )
    (net (code "84") (name "Net-(T1-MCT1)") (class "Default")
      (node (ref "R45") (pin "1") (pinfunction "1_1") (pintype "passive"))
      (node (ref "T1") (pin "24") (pinfunction "MCT1_24") (pintype "passive"))
    )
    (net (code "85") (name "Net-(T1-MCT2)") (class "Default")
      (node (ref "R46") (pin "1") (pinfunction "1_1") (pintype "passive"))
      (node (ref "T1") (pin "21") (pinfunction "MCT2_21") (pintype "passive"))
    )
    (net (code "86") (name "Net-(T1-MCT3)") (class "Default")
      (node (ref "R47") (pin "1") (pinfunction "1_1") (pintype "passive"))
      (node (ref "T1") (pin "18") (pinfunction "MCT3_18") (pintype "passive"))
    )
    (net (code "87") (name "Net-(T1-MCT4)") (class "Default")
      (node (ref "R48") (pin "1") (pinfunction "1_1") (pintype "passive"))
      (node (ref "T1") (pin "15") (pinfunction "MCT4_15") (pintype "passive"))
    )
    (net (code "88") (name "Net-(T1-TCT1)") (class "Default")
      (node (ref "C39") (pin "1") (pinfunction "1_1") (pintype "passive"))
      (node (ref "T1") (pin "1") (pinfunction "TCT1_1") (pintype "passive"))
    )
    (net (code "89") (name "Net-(T1-TCT2)") (class "Default")
      (node (ref "C40") (pin "1") (pinfunction "1_1") (pintype "passive"))
      (node (ref "T1") (pin "4") (pinfunction "TCT2_4") (pintype "passive"))
    )
    (net (code "90") (name "Net-(T1-TCT3)") (class "Default")
      (node (ref "C41") (pin "1") (pinfunction "1_1") (pintype "passive"))
      (node (ref "T1") (pin "7") (pinfunction "TCT3_7") (pintype "passive"))
    )
    (net (code "91") (name "Net-(T1-TCT4)") (class "Default")
      (node (ref "C42") (pin "1") (pinfunction "1_1") (pintype "passive"))
      (node (ref "T1") (pin "10") (pinfunction "TCT4_10") (pintype "passive"))
    )
    (net (code "92") (name "Net-(T2-1_MCT1)") (class "Default")
      (node (ref "R49") (pin "1") (pinfunction "1_1") (pintype "passive"))
      (node (ref "T2") (pin "48") (pinfunction "1_MCT1_48") (pintype "input"))
    )
    (net (code "93") (name "Net-(T2-1_MCT2)") (class "Default")
      (node (ref "R50") (pin "1") (pinfunction "1_1") (pintype "passive"))
      (node (ref "T2") (pin "45") (pinfunction "1_MCT2_45") (pintype "input"))
    )
    (net (code "94") (name "Net-(T2-1_MCT3)") (class "Default")
      (node (ref "R51") (pin "1") (pinfunction "1_1") (pintype "passive"))
      (node (ref "T2") (pin "42") (pinfunction "1_MCT3_42") (pintype "input"))
    )
    (net (code "95") (name "Net-(T2-1_MCT4)") (class "Default")
      (node (ref "R52") (pin "1") (pinfunction "1_1") (pintype "passive"))
      (node (ref "T2") (pin "39") (pinfunction "1_MCT4_39") (pintype "input"))
    )
    (net (code "96") (name "Net-(T2-1_TCT1)") (class "Default")
      (node (ref "C45") (pin "1") (pinfunction "1_1") (pintype "passive"))
      (node (ref "T2") (pin "1") (pinfunction "1_TCT1_1") (pintype "input"))
    )
    (net (code "97") (name "Net-(T2-1_TCT2)") (class "Default")
      (node (ref "C46") (pin "1") (pinfunction "1_1") (pintype "passive"))
      (node (ref "T2") (pin "4") (pinfunction "1_TCT2_4") (pintype "input"))
    )
    (net (code "98") (name "Net-(T2-1_TCT3)") (class "Default")
      (node (ref "C48") (pin "1") (pinfunction "1_1") (pintype "passive"))
      (node (ref "T2") (pin "7") (pinfunction "1_TCT3_7") (pintype "input"))
    )
    (net (code "99") (name "Net-(T2-1_TCT4)") (class "Default")
      (node (ref "C49") (pin "1") (pinfunction "1_1") (pintype "passive"))
      (node (ref "T2") (pin "10") (pinfunction "1_TCT4_10") (pintype "input"))
    )
    (net (code "100") (name "Net-(T2-2_MCT5)") (class "Default")
      (node (ref "R53") (pin "1") (pinfunction "1_1") (pintype "passive"))
      (node (ref "T2") (pin "36") (pinfunction "2_MCT5_36") (pintype "input"))
    )
    (net (code "101") (name "Net-(T2-2_MCT6)") (class "Default")
      (node (ref "R54") (pin "1") (pinfunction "1_1") (pintype "passive"))
      (node (ref "T2") (pin "33") (pinfunction "2_MCT6_33") (pintype "input"))
    )
    (net (code "102") (name "Net-(T2-2_MCT7)") (class "Default")
      (node (ref "R55") (pin "1") (pinfunction "1_1") (pintype "passive"))
      (node (ref "T2") (pin "30") (pinfunction "2_MCT7_30") (pintype "input"))
    )
    (net (code "103") (name "Net-(T2-2_MCT8)") (class "Default")
      (node (ref "R56") (pin "1") (pinfunction "1_1") (pintype "passive"))
      (node (ref "T2") (pin "27") (pinfunction "2_MCT8_27") (pintype "input"))
    )
    (net (code "104") (name "Net-(T2-2_TCT5)") (class "Default")
      (node (ref "C50") (pin "1") (pinfunction "1_1") (pintype "passive"))
      (node (ref "T2") (pin "13") (pinfunction "2_TCT5_13") (pintype "input"))
    )
    (net (code "105") (name "Net-(T2-2_TCT6)") (class "Default")
      (node (ref "C51") (pin "1") (pinfunction "1_1") (pintype "passive"))
      (node (ref "T2") (pin "16") (pinfunction "2_TCT6_16") (pintype "input"))
    )
    (net (code "106") (name "Net-(T2-2_TCT7)") (class "Default")
      (node (ref "C53") (pin "1") (pinfunction "1_1") (pintype "passive"))
      (node (ref "T2") (pin "19") (pinfunction "2_TCT7_19") (pintype "input"))
    )
    (net (code "107") (name "Net-(T2-2_TCT8)") (class "Default")
      (node (ref "C54") (pin "1") (pinfunction "1_1") (pintype "passive"))
      (node (ref "T2") (pin "22") (pinfunction "2_TCT8_22") (pintype "input"))
    )
    (net (code "108") (name "Net-(T3-1_MCT1)") (class "Default")
      (node (ref "R57") (pin "1") (pinfunction "1_1") (pintype "passive"))
      (node (ref "T3") (pin "48") (pinfunction "1_MCT1_48") (pintype "input"))
    )
    (net (code "109") (name "Net-(T3-1_MCT2)") (class "Default")
      (node (ref "R58") (pin "1") (pinfunction "1_1") (pintype "passive"))
      (node (ref "T3") (pin "45") (pinfunction "1_MCT2_45") (pintype "input"))
    )
    (net (code "110") (name "Net-(T3-1_MCT3)") (class "Default")
      (node (ref "R59") (pin "1") (pinfunction "1_1") (pintype "passive"))
      (node (ref "T3") (pin "42") (pinfunction "1_MCT3_42") (pintype "input"))
    )
    (net (code "111") (name "Net-(T3-1_MCT4)") (class "Default")
      (node (ref "R60") (pin "1") (pinfunction "1_1") (pintype "passive"))
      (node (ref "T3") (pin "39") (pinfunction "1_MCT4_39") (pintype "input"))
    )
    (net (code "112") (name "Net-(T3-1_TCT1)") (class "Default")
      (node (ref "C56") (pin "1") (pinfunction "1_1") (pintype "passive"))
      (node (ref "T3") (pin "1") (pinfunction "1_TCT1_1") (pintype "input"))
    )
    (net (code "113") (name "Net-(T3-1_TCT2)") (class "Default")
      (node (ref "C57") (pin "1") (pinfunction "1_1") (pintype "passive"))
      (node (ref "T3") (pin "4") (pinfunction "1_TCT2_4") (pintype "input"))
    )
    (net (code "114") (name "Net-(T3-1_TCT3)") (class "Default")
      (node (ref "C58") (pin "1") (pinfunction "1_1") (pintype "passive"))
      (node (ref "T3") (pin "7") (pinfunction "1_TCT3_7") (pintype "input"))
    )
    (net (code "115") (name "Net-(T3-1_TCT4)") (class "Default")
      (node (ref "C59") (pin "1") (pinfunction "1_1") (pintype "passive"))
      (node (ref "T3") (pin "10") (pinfunction "1_TCT4_10") (pintype "input"))
    )
    (net (code "116") (name "Net-(T3-2_MCT5)") (class "Default")
      (node (ref "R61") (pin "1") (pinfunction "1_1") (pintype "passive"))
      (node (ref "T3") (pin "36") (pinfunction "2_MCT5_36") (pintype "input"))
    )
    (net (code "117") (name "Net-(T3-2_MCT6)") (class "Default")
      (node (ref "R62") (pin "1") (pinfunction "1_1") (pintype "passive"))
      (node (ref "T3") (pin "33") (pinfunction "2_MCT6_33") (pintype "input"))
    )
    (net (code "118") (name "Net-(T3-2_MCT7)") (class "Default")
      (node (ref "R63") (pin "1") (pinfunction "1_1") (pintype "passive"))
      (node (ref "T3") (pin "30") (pinfunction "2_MCT7_30") (pintype "input"))
    )
    (net (code "119") (name "Net-(T3-2_MCT8)") (class "Default")
      (node (ref "R64") (pin "1") (pinfunction "1_1") (pintype "passive"))
      (node (ref "T3") (pin "27") (pinfunction "2_MCT8_27") (pintype "input"))
    )
    (net (code "120") (name "Net-(T3-2_TCT5)") (class "Default")
      (node (ref "C60") (pin "1") (pinfunction "1_1") (pintype "passive"))
      (node (ref "T3") (pin "13") (pinfunction "2_TCT5_13") (pintype "input"))
    )
    (net (code "121") (name "Net-(T3-2_TCT6)") (class "Default")
      (node (ref "C61") (pin "1") (pinfunction "1_1") (pintype "passive"))
      (node (ref "T3") (pin "16") (pinfunction "2_TCT6_16") (pintype "input"))
    )
    (net (code "122") (name "Net-(T3-2_TCT7)") (class "Default")
      (node (ref "C62") (pin "1") (pinfunction "1_1") (pintype "passive"))
      (node (ref "T3") (pin "19") (pinfunction "2_TCT7_19") (pintype "input"))
    )
    (net (code "123") (name "Net-(T3-2_TCT8)") (class "Default")
      (node (ref "C63") (pin "1") (pinfunction "1_1") (pintype "passive"))
      (node (ref "T3") (pin "22") (pinfunction "2_TCT8_22") (pintype "input"))
    )
    (net (code "124") (name "unconnected-(CN2-Case1-Pad9)") (class "Default")
      (node (ref "CN2") (pin "9") (pinfunction "Case1_9") (pintype "passive+no_connect"))
    )
    (net (code "125") (name "unconnected-(CN2-Case2-Pad10)") (class "Default")
      (node (ref "CN2") (pin "10") (pinfunction "Case2_10") (pintype "passive+no_connect"))
    )
    (net (code "126") (name "unconnected-(P1-Pad33)") (class "Default")
      (node (ref "P1") (pin "33") (pinfunction "33_33") (pintype "passive+no_connect"))
    )
    (net (code "127") (name "unconnected-(P1-Pad34)") (class "Default")
      (node (ref "P1") (pin "34") (pinfunction "34_34") (pintype "passive+no_connect"))
    )
  )
)
